# MAC_PHY_shield.net
KiCad netlist of a schematic drawn in EAGLE
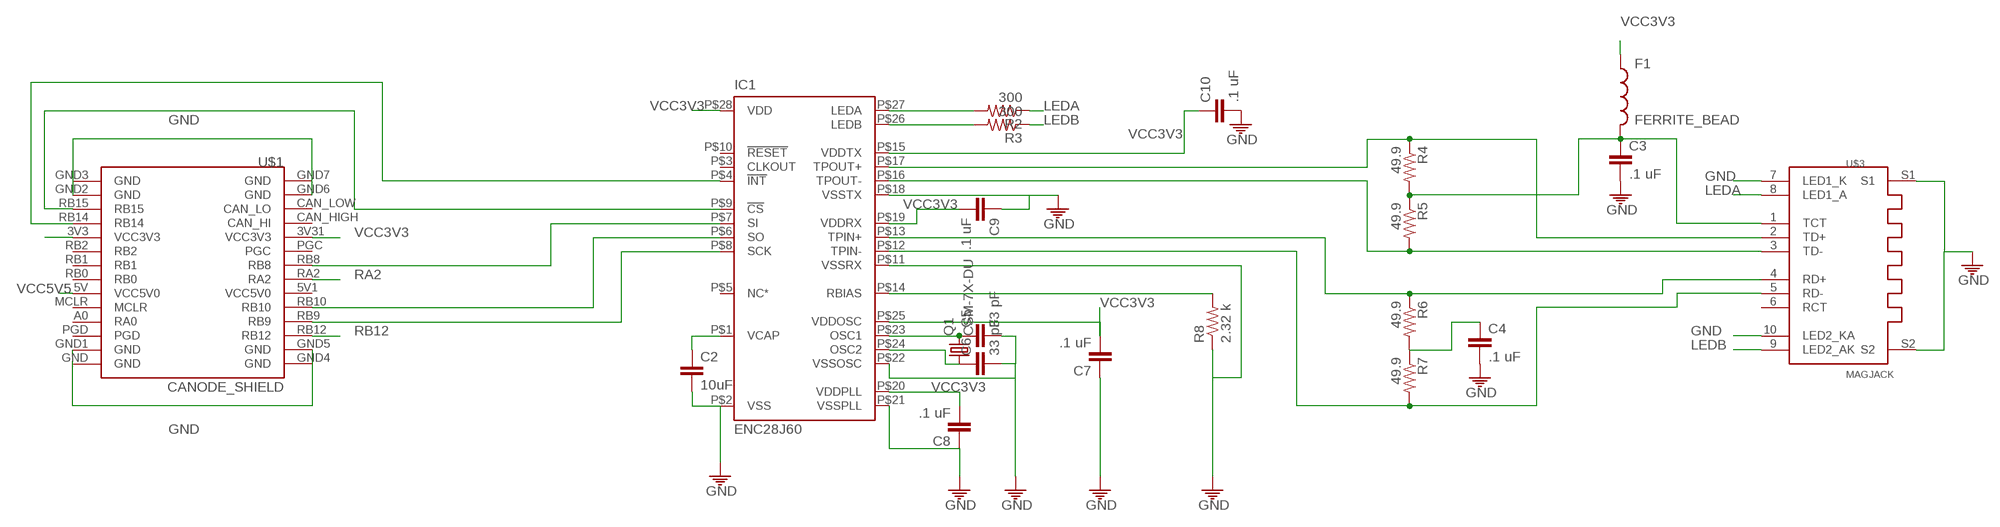
[diagram p0: schematic, sheet 1]

(export (version "E")
  (design (tool "Eeschema 10.0.6"))
  (components
    (comp (ref "C2")
      (value "10uF")
      (footprint "eagle-import:1206")
      (libsource (lib "eagle-import") (part "CAP1206"))
    )
    (comp (ref "C3")
      (value ".1 uF")
      (footprint "eagle-import:1206")
      (libsource (lib "eagle-import") (part "CAP1206"))
    )
    (comp (ref "C4")
      (value ".1 uF")
      (footprint "eagle-import:1206")
      (libsource (lib "eagle-import") (part "CAP1206"))
    )
    (comp (ref "C5")
      (value "33 pF")
      (footprint "eagle-import:1206")
      (libsource (lib "eagle-import") (part "CAP1206"))
    )
    (comp (ref "C6")
      (value "33 pF")
      (footprint "eagle-import:1206")
      (libsource (lib "eagle-import") (part "CAP1206"))
    )
    (comp (ref "C7")
      (value ".1 uF")
      (footprint "eagle-import:1206")
      (libsource (lib "eagle-import") (part "CAP1206"))
    )
    (comp (ref "C8")
      (value ".1 uF")
      (footprint "eagle-import:1206")
      (libsource (lib "eagle-import") (part "CAP1206"))
    )
    (comp (ref "C9")
      (value ".1 uF")
      (footprint "eagle-import:1206")
      (libsource (lib "eagle-import") (part "CAP1206"))
    )
    (comp (ref "C10")
      (value ".1 uF")
      (footprint "eagle-import:1206")
      (libsource (lib "eagle-import") (part "CAP1206"))
    )
    (comp (ref "F1")
      (value "FERRITE_BEAD")
      (footprint "eagle-import:1206")
      (libsource (lib "eagle-import") (part "FERRITE_BEAD"))
    )
    (comp (ref "IC1")
      (value "ENC28J60")
      (footprint "eagle-import:SOIC28-W")
      (libsource (lib "eagle-import") (part "ENC28J60"))
    )
    (comp (ref "Q1")
      (value "CSM-7X-DU")
      (footprint "eagle-import:CSM-7X-DU")
      (libsource (lib "eagle-import") (part "CSM-7X-DU"))
    )
    (comp (ref "R2")
      (value "300")
      (footprint "eagle-import:0805")
      (libsource (lib "eagle-import") (part "RESISTOR0805-RES"))
    )
    (comp (ref "R3")
      (value "300")
      (footprint "eagle-import:0805")
      (libsource (lib "eagle-import") (part "RESISTOR0805-RES"))
    )
    (comp (ref "R4")
      (value "49.9")
      (footprint "eagle-import:0805")
      (libsource (lib "eagle-import") (part "RESISTOR0805-RES"))
    )
    (comp (ref "R5")
      (value "49.9")
      (footprint "eagle-import:0805")
      (libsource (lib "eagle-import") (part "RESISTOR0805-RES"))
    )
    (comp (ref "R6")
      (value "49.9")
      (footprint "eagle-import:0805")
      (libsource (lib "eagle-import") (part "RESISTOR0805-RES"))
    )
    (comp (ref "R7")
      (value "49.9")
      (footprint "eagle-import:0805")
      (libsource (lib "eagle-import") (part "RESISTOR0805-RES"))
    )
    (comp (ref "R8")
      (value "2.32 k")
      (footprint "eagle-import:0805")
      (libsource (lib "eagle-import") (part "RESISTOR0805-RES"))
    )
    (comp (ref "U$1")
      (value "CANODE_SHIELD")
      (footprint "eagle-import:CANODE_SHIELD")
      (libsource (lib "eagle-import") (part "CANODE_SHIELD"))
    )
    (comp (ref "U$3")
      (value "MAGJACK")
      (footprint "eagle-import:08B0-1X1T-06-F")
      (libsource (lib "eagle-import") (part "MAGJACK"))
    )
  )
  (nets
    (net (code "1") (name "/LEDA") (class "Default")
      (node (ref "R2") (pin "1") (pinfunction "1_1") (pintype "passive"))
      (node (ref "U$3") (pin "8") (pinfunction "LED1_A_8") (pintype "bidirectional"))
    )
    (net (code "2") (name "/LEDB") (class "Default")
      (node (ref "R3") (pin "1") (pinfunction "1_1") (pintype "passive"))
      (node (ref "U$3") (pin "9") (pinfunction "LED2_AK_9") (pintype "bidirectional"))
    )
    (net (code "3") (name "/RA2") (class "Default")
      (node (ref "U$1") (pin "RA2") (pinfunction "RA2_RA2") (pintype "bidirectional"))
    )
    (net (code "4") (name "/RB12") (class "Default")
      (node (ref "U$1") (pin "RB12") (pinfunction "RB12_RB12") (pintype "bidirectional"))
    )
    (net (code "5") (name "/VCC3V3") (class "Default")
      (node (ref "C10") (pin "1") (pinfunction "1_1") (pintype "passive"))
      (node (ref "C7") (pin "2") (pinfunction "2_2") (pintype "passive"))
      (node (ref "C8") (pin "2") (pinfunction "2_2") (pintype "passive"))
      (node (ref "C9") (pin "2") (pinfunction "2_2") (pintype "passive"))
      (node (ref "F1") (pin "1") (pinfunction "1_1") (pintype "passive"))
      (node (ref "IC1") (pin "P$15") (pinfunction "VDDTX_P$15") (pintype "input"))
      (node (ref "IC1") (pin "P$19") (pinfunction "VDDRX_P$19") (pintype "input"))
      (node (ref "IC1") (pin "P$20") (pinfunction "VDDPLL_P$20") (pintype "input"))
      (node (ref "IC1") (pin "P$25") (pinfunction "VDDOSC_P$25") (pintype "input"))
      (node (ref "IC1") (pin "P$28") (pinfunction "VDD_P$28") (pintype "input"))
      (node (ref "U$1") (pin "3V3") (pinfunction "VCC3V3_3V3") (pintype "bidirectional"))
      (node (ref "U$1") (pin "3V31") (pinfunction "VCC3V3_3V31") (pintype "bidirectional"))
    )
    (net (code "6") (name "/VCC5V5") (class "Default")
      (node (ref "U$1") (pin "5V") (pinfunction "VCC5V0_5V") (pintype "bidirectional"))
    )
    (net (code "7") (name "GND") (class "Default")
      (node (ref "C10") (pin "2") (pinfunction "2_2") (pintype "passive"))
      (node (ref "C2") (pin "2") (pinfunction "2_2") (pintype "passive"))
      (node (ref "C3") (pin "2") (pinfunction "2_2") (pintype "passive"))
      (node (ref "C4") (pin "2") (pinfunction "2_2") (pintype "passive"))
      (node (ref "C5") (pin "2") (pinfunction "2_2") (pintype "passive"))
      (node (ref "C6") (pin "2") (pinfunction "2_2") (pintype "passive"))
      (node (ref "C7") (pin "1") (pinfunction "1_1") (pintype "passive"))
      (node (ref "C8") (pin "1") (pinfunction "1_1") (pintype "passive"))
      (node (ref "C9") (pin "1") (pinfunction "1_1") (pintype "passive"))
      (node (ref "IC1") (pin "P$11") (pinfunction "VSSRX_P$11") (pintype "input"))
      (node (ref "IC1") (pin "P$18") (pinfunction "VSSTX_P$18") (pintype "input"))
      (node (ref "IC1") (pin "P$2") (pinfunction "VSS_P$2") (pintype "input"))
      (node (ref "IC1") (pin "P$21") (pinfunction "VSSPLL_P$21") (pintype "input"))
      (node (ref "IC1") (pin "P$22") (pinfunction "VSSOSC_P$22") (pintype "input"))
      (node (ref "R8") (pin "1") (pinfunction "1_1") (pintype "passive"))
      (node (ref "U$1") (pin "GND") (pinfunction "GND_GND") (pintype "bidirectional"))
      (node (ref "U$1") (pin "GND1") (pinfunction "GND_GND1") (pintype "bidirectional"))
      (node (ref "U$1") (pin "GND2") (pinfunction "GND_GND2") (pintype "bidirectional"))
      (node (ref "U$1") (pin "GND3") (pinfunction "GND_GND3") (pintype "bidirectional"))
      (node (ref "U$1") (pin "GND4") (pinfunction "GND_GND4") (pintype "bidirectional"))
      (node (ref "U$1") (pin "GND5") (pinfunction "GND_GND5") (pintype "bidirectional"))
      (node (ref "U$1") (pin "GND6") (pinfunction "GND_GND6") (pintype "bidirectional"))
      (node (ref "U$1") (pin "GND7") (pinfunction "GND_GND7") (pintype "bidirectional"))
      (node (ref "U$3") (pin "10") (pinfunction "LED2_KA_10") (pintype "bidirectional"))
      (node (ref "U$3") (pin "7") (pinfunction "LED1_K_7") (pintype "bidirectional"))
      (node (ref "U$3") (pin "S1") (pinfunction "S1_S1") (pintype "bidirectional"))
      (node (ref "U$3") (pin "S2") (pinfunction "S2_S2") (pintype "bidirectional"))
    )
    (net (code "8") (name "Net-(C4-Pad1)") (class "Default")
      (node (ref "C4") (pin "1") (pinfunction "1_1") (pintype "passive"))
      (node (ref "R6") (pin "2") (pinfunction "2_2") (pintype "passive"))
      (node (ref "R7") (pin "1") (pinfunction "1_1") (pintype "passive"))
    )
    (net (code "9") (name "Net-(IC1-LEDA)") (class "Default")
      (node (ref "IC1") (pin "P$27") (pinfunction "LEDA_P$27") (pintype "output"))
      (node (ref "R2") (pin "2") (pinfunction "2_2") (pintype "passive"))
    )
    (net (code "10") (name "Net-(IC1-LEDB)") (class "Default")
      (node (ref "IC1") (pin "P$26") (pinfunction "LEDB_P$26") (pintype "output"))
      (node (ref "R3") (pin "2") (pinfunction "2_2") (pintype "passive"))
    )
    (net (code "11") (name "Net-(IC1-OSC1)") (class "Default")
      (node (ref "C5") (pin "1") (pinfunction "1_1") (pintype "passive"))
      (node (ref "IC1") (pin "P$23") (pinfunction "OSC1_P$23") (pintype "input"))
      (node (ref "Q1") (pin "2") (pinfunction "2_2") (pintype "passive"))
    )
    (net (code "12") (name "Net-(IC1-OSC2)") (class "Default")
      (node (ref "C6") (pin "1") (pinfunction "1_1") (pintype "passive"))
      (node (ref "IC1") (pin "P$24") (pinfunction "OSC2_P$24") (pintype "output"))
      (node (ref "Q1") (pin "1") (pinfunction "1_1") (pintype "passive"))
    )
    (net (code "13") (name "Net-(IC1-RBIAS)") (class "Default")
      (node (ref "IC1") (pin "P$14") (pinfunction "RBIAS_P$14") (pintype "input"))
      (node (ref "R8") (pin "2") (pinfunction "2_2") (pintype "passive"))
    )
    (net (code "14") (name "Net-(IC1-SCK)") (class "Default")
      (node (ref "IC1") (pin "P$8") (pinfunction "SCK_P$8") (pintype "input"))
      (node (ref "U$1") (pin "RB9") (pinfunction "RB9_RB9") (pintype "bidirectional"))
    )
    (net (code "15") (name "Net-(IC1-SI)") (class "Default")
      (node (ref "IC1") (pin "P$7") (pinfunction "SI_P$7") (pintype "input"))
      (node (ref "U$1") (pin "RB8") (pinfunction "RB8_RB8") (pintype "bidirectional"))
    )
    (net (code "16") (name "Net-(IC1-SO)") (class "Default")
      (node (ref "IC1") (pin "P$6") (pinfunction "SO_P$6") (pintype "output"))
      (node (ref "U$1") (pin "RB10") (pinfunction "RB10_RB10") (pintype "bidirectional"))
    )
    (net (code "17") (name "Net-(IC1-TPIN+)") (class "Default")
      (node (ref "IC1") (pin "P$13") (pinfunction "TPIN+_P$13") (pintype "input"))
      (node (ref "R6") (pin "1") (pinfunction "1_1") (pintype "passive"))
      (node (ref "U$3") (pin "4") (pinfunction "RD+_4") (pintype "bidirectional"))
    )
    (net (code "18") (name "Net-(IC1-TPIN-)") (class "Default")
      (node (ref "IC1") (pin "P$12") (pinfunction "TPIN-_P$12") (pintype "input"))
      (node (ref "R7") (pin "2") (pinfunction "2_2") (pintype "passive"))
      (node (ref "U$3") (pin "5") (pinfunction "RD-_5") (pintype "bidirectional"))
    )
    (net (code "19") (name "Net-(IC1-TPOUT+)") (class "Default")
      (node (ref "IC1") (pin "P$17") (pinfunction "TPOUT+_P$17") (pintype "output"))
      (node (ref "R4") (pin "1") (pinfunction "1_1") (pintype "passive"))
      (node (ref "U$3") (pin "2") (pinfunction "TD+_2") (pintype "bidirectional"))
    )
    (net (code "20") (name "Net-(IC1-TPOUT-)") (class "Default")
      (node (ref "IC1") (pin "P$16") (pinfunction "TPOUT-_P$16") (pintype "output"))
      (node (ref "R5") (pin "2") (pinfunction "2_2") (pintype "passive"))
      (node (ref "U$3") (pin "3") (pinfunction "TD-_3") (pintype "bidirectional"))
    )
    (net (code "21") (name "Net-(IC1-VCAP)") (class "Default")
      (node (ref "C2") (pin "1") (pinfunction "1_1") (pintype "passive"))
      (node (ref "IC1") (pin "P$1") (pinfunction "VCAP_P$1") (pintype "input"))
    )
    (net (code "22") (name "Net-(IC1-~{CS})") (class "Default")
      (node (ref "IC1") (pin "P$9") (pinfunction "~{CS}_P$9") (pintype "input"))
      (node (ref "U$1") (pin "RB15") (pinfunction "RB15_RB15") (pintype "bidirectional"))
    )
    (net (code "23") (name "Net-(IC1-~{INT})") (class "Default")
      (node (ref "IC1") (pin "P$4") (pinfunction "~{INT}_P$4") (pintype "output"))
      (node (ref "U$1") (pin "RB14") (pinfunction "RB14_RB14") (pintype "bidirectional"))
    )
    (net (code "24") (name "Net-(U$3-TCT)") (class "Default")
      (node (ref "C3") (pin "1") (pinfunction "1_1") (pintype "passive"))
      (node (ref "F1") (pin "2") (pinfunction "2_2") (pintype "passive"))
      (node (ref "R4") (pin "2") (pinfunction "2_2") (pintype "passive"))
      (node (ref "R5") (pin "1") (pinfunction "1_1") (pintype "passive"))
      (node (ref "U$3") (pin "1") (pinfunction "TCT_1") (pintype "bidirectional"))
    )
    (net (code "25") (name "unconnected-(IC1-CLKOUT-PadP$3)") (class "Default")
      (node (ref "IC1") (pin "P$3") (pinfunction "CLKOUT_P$3") (pintype "output"))
    )
    (net (code "26") (name "unconnected-(IC1-NC*-PadP$5)") (class "Default")
      (node (ref "IC1") (pin "P$5") (pinfunction "NC*_P$5") (pintype "output"))
    )
    (net (code "27") (name "unconnected-(IC1-~{RESET}-PadP$10)") (class "Default")
      (node (ref "IC1") (pin "P$10") (pinfunction "~{RESET}_P$10") (pintype "input"))
    )
    (net (code "28") (name "unconnected-(U$1-CAN_HI-PadCAN_HIGH)") (class "Default")
      (node (ref "U$1") (pin "CAN_HIGH") (pinfunction "CAN_HI_CAN_HIGH") (pintype "bidirectional"))
    )
    (net (code "29") (name "unconnected-(U$1-CAN_LO-PadCAN_LOW)") (class "Default")
      (node (ref "U$1") (pin "CAN_LOW") (pinfunction "CAN_LO_CAN_LOW") (pintype "bidirectional"))
    )
    (net (code "30") (name "unconnected-(U$1-PadMCLR)") (class "Default")
      (node (ref "U$1") (pin "MCLR") (pinfunction "MCLR_MCLR") (pintype "bidirectional"))
    )
    (net (code "31") (name "unconnected-(U$1-PadPGC)") (class "Default")
      (node (ref "U$1") (pin "PGC") (pinfunction "PGC_PGC") (pintype "bidirectional"))
    )
    (net (code "32") (name "unconnected-(U$1-PadPGD)") (class "Default")
      (node (ref "U$1") (pin "PGD") (pinfunction "PGD_PGD") (pintype "bidirectional"))
    )
    (net (code "33") (name "unconnected-(U$1-PadRB0)") (class "Default")
      (node (ref "U$1") (pin "RB0") (pinfunction "RB0_RB0") (pintype "bidirectional"))
    )
    (net (code "34") (name "unconnected-(U$1-PadRB1)") (class "Default")
      (node (ref "U$1") (pin "RB1") (pinfunction "RB1_RB1") (pintype "bidirectional"))
    )
    (net (code "35") (name "unconnected-(U$1-PadRB2)") (class "Default")
      (node (ref "U$1") (pin "RB2") (pinfunction "RB2_RB2") (pintype "bidirectional"))
    )
    (net (code "36") (name "unconnected-(U$1-RA0-PadA0)") (class "Default")
      (node (ref "U$1") (pin "A0") (pinfunction "RA0_A0") (pintype "bidirectional"))
    )
    (net (code "37") (name "unconnected-(U$1-VCC5V0-Pad5V1)") (class "Default")
      (node (ref "U$1") (pin "5V1") (pinfunction "VCC5V0_5V1") (pintype "bidirectional"))
    )
    (net (code "38") (name "unconnected-(U$3-RCT-Pad6)") (class "Default")
      (node (ref "U$3") (pin "6") (pinfunction "RCT_6") (pintype "bidirectional"))
    )
  )
)
